# THB.net
KiCad netlist of a schematic drawn in Altium Designer
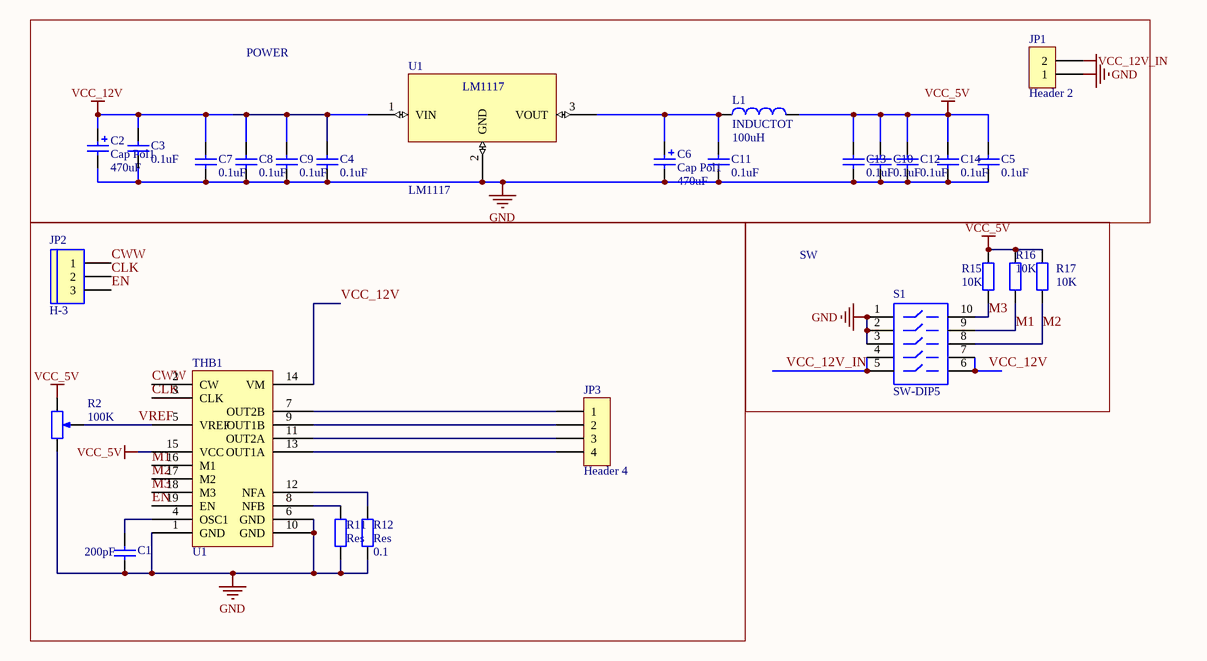
[diagram p0: THB.SchDoc]

(export (version "E")
  (design (tool "Eeschema 10.0.6"))
  (components
    (comp (ref "C1")
      (value "200pF")
      (footprint "CC1005-0402")
      (description "Capacitor")
      (fields
        (field (name "MANUFACTURER") "Generic Components")
        (field (name "Comment") "CAP")
        (field (name "PUBLISHER") "Altium Hobart Technology Centre")
      )
      (libsource (lib "HGH") (part "CAP"))
    )
    (comp (ref "C2")
      (value "Cap Pol1")
      (footprint "diode stan")
      (description "Polarized Capacitor (Radial)")
      (fields
        (field (name "MANUFACTURER") "Generic Components")
        (field (name "ALTIUM_VALUE") "470uF")
        (field (name "PUBLISHER") "Altium Hobart Technology Centre")
      )
      (libsource (lib "HGH") (part "Cap Pol1"))
    )
    (comp (ref "C3")
      (value "0.1uF")
      (footprint "CC1005-0402")
      (description "Capacitor")
      (fields
        (field (name "MANUFACTURER") "Generic Components")
        (field (name "Comment") "CAP_1")
        (field (name "PUBLISHER") "Altium Hobart Technology Centre")
      )
      (libsource (lib "My SchLib") (part "CAP_1"))
    )
    (comp (ref "C4")
      (value "0.1uF")
      (footprint "CC1005-0402")
      (description "Capacitor")
      (fields
        (field (name "MANUFACTURER") "Generic Components")
        (field (name "Comment") "CAP")
        (field (name "PUBLISHER") "Altium Hobart Technology Centre")
      )
      (libsource (lib "HGH") (part "CAP"))
    )
    (comp (ref "C5")
      (value "0.1uF")
      (footprint "CC1005-0402")
      (description "Capacitor")
      (fields
        (field (name "MANUFACTURER") "Generic Components")
        (field (name "Comment") "CAP")
        (field (name "PUBLISHER") "Altium Hobart Technology Centre")
      )
      (libsource (lib "HGH") (part "CAP"))
    )
    (comp (ref "C6")
      (value "Cap Pol1")
      (footprint "diode stan")
      (description "Polarized Capacitor (Radial)")
      (fields
        (field (name "MANUFACTURER") "Generic Components")
        (field (name "ALTIUM_VALUE") "470uF")
        (field (name "PUBLISHER") "Altium Hobart Technology Centre")
      )
      (libsource (lib "HGH") (part "Cap Pol1"))
    )
    (comp (ref "C7")
      (value "0.1uF")
      (footprint "CC1005-0402")
      (description "Capacitor")
      (fields
        (field (name "MANUFACTURER") "Generic Components")
        (field (name "Comment") "CAP_1")
        (field (name "PUBLISHER") "Altium Hobart Technology Centre")
      )
      (libsource (lib "My SchLib") (part "CAP_1"))
    )
    (comp (ref "C8")
      (value "0.1uF")
      (footprint "CC1005-0402")
      (description "Capacitor")
      (fields
        (field (name "MANUFACTURER") "Generic Components")
        (field (name "Comment") "CAP_1")
        (field (name "PUBLISHER") "Altium Hobart Technology Centre")
      )
      (libsource (lib "My SchLib") (part "CAP_1"))
    )
    (comp (ref "C9")
      (value "0.1uF")
      (footprint "CC1005-0402")
      (description "Capacitor")
      (fields
        (field (name "MANUFACTURER") "Generic Components")
        (field (name "Comment") "CAP_1")
        (field (name "PUBLISHER") "Altium Hobart Technology Centre")
      )
      (libsource (lib "My SchLib") (part "CAP_1"))
    )
    (comp (ref "C10")
      (value "0.1uF")
      (footprint "CC1005-0402")
      (description "Capacitor")
      (fields
        (field (name "MANUFACTURER") "Generic Components")
        (field (name "Comment") "CAP_1")
        (field (name "PUBLISHER") "Altium Hobart Technology Centre")
      )
      (libsource (lib "My SchLib") (part "CAP_1"))
    )
    (comp (ref "C11")
      (value "0.1uF")
      (footprint "CC1005-0402")
      (description "Capacitor")
      (fields
        (field (name "MANUFACTURER") "Generic Components")
        (field (name "Comment") "CAP_1")
        (field (name "PUBLISHER") "Altium Hobart Technology Centre")
      )
      (libsource (lib "My SchLib") (part "CAP_1"))
    )
    (comp (ref "C12")
      (value "0.1uF")
      (footprint "CC1005-0402")
      (description "Capacitor")
      (fields
        (field (name "MANUFACTURER") "Generic Components")
        (field (name "Comment") "CAP_1")
        (field (name "PUBLISHER") "Altium Hobart Technology Centre")
      )
      (libsource (lib "My SchLib") (part "CAP_1"))
    )
    (comp (ref "C13")
      (value "0.1uF")
      (footprint "CC1005-0402")
      (description "Capacitor")
      (fields
        (field (name "MANUFACTURER") "Generic Components")
        (field (name "Comment") "CAP_1")
        (field (name "PUBLISHER") "Altium Hobart Technology Centre")
      )
      (libsource (lib "My SchLib") (part "CAP_1"))
    )
    (comp (ref "C14")
      (value "0.1uF")
      (footprint "CC1005-0402")
      (description "Capacitor")
      (fields
        (field (name "MANUFACTURER") "Generic Components")
        (field (name "Comment") "CAP_1")
        (field (name "PUBLISHER") "Altium Hobart Technology Centre")
      )
      (libsource (lib "My SchLib") (part "CAP_1"))
    )
    (comp (ref "JP1")
      (value "Header 2")
      (footprint "HDR1-2")
      (description "Header, 2-Pin")
      (fields (field (name "MANUFACTURER") "Generic Components"))
      (libsource (lib "HGH") (part "Header 2"))
    )
    (comp (ref "JP2")
      (value "H-3")
      (footprint "H- 3")
      (description "Header, 3-Pin")
      (fields (field (name "MANUFACTURER") "Generic Components"))
      (libsource (lib "HGH") (part "H-3"))
    )
    (comp (ref "JP3")
      (value "Header 4")
      (footprint "HDR1-4")
      (description "Header, 4-Pin")
      (fields (field (name "MANUFACTURER") "Generic Components"))
      (libsource (lib "HGH") (part "Header 4"))
    )
    (comp (ref "L1")
      (value "INDUCTOT")
      (footprint "贴片电感")
      (description "Inductor")
      (fields
        (field (name "MANUFACTURER") "Generic Components")
        (field (name "ALTIUM_VALUE") "100uH")
        (field (name "PUBLISHER") "Altium Hobart Technology Centre")
      )
      (libsource (lib "HGH") (part "INDUCTOT"))
    )
    (comp (ref "R2")
      (value "100K")
      (footprint "res-adj-tiepian")
      (description "Potentiometer")
      (fields (field (name "Comment") "RES-Pot2"))
      (libsource (lib "HGH") (part "RES-Pot2"))
    )
    (comp (ref "R11")
      (value "Res")
      (footprint "AXLAL0.4")
      (description "Resistor")
      (fields
        (field (name "MANUFACTURER") "Generic Components")
        (field (name "PUBLISHER") "Altium Hobart Technology Centre")
      )
      (libsource (lib "HGH") (part "Res"))
    )
    (comp (ref "R12")
      (value "Res")
      (footprint "AXLAL0.4")
      (description "Resistor")
      (fields
        (field (name "MANUFACTURER") "Generic Components")
        (field (name "ALTIUM_VALUE") "0.1")
        (field (name "PUBLISHER") "Altium Hobart Technology Centre")
      )
      (libsource (lib "HGH") (part "Res"))
    )
    (comp (ref "R15")
      (value "10K")
      (footprint "R2012-0805")
      (description "Resistor")
      (fields
        (field (name "MANUFACTURER") "Generic Components")
        (field (name "Comment") "Res")
        (field (name "PUBLISHER") "Altium Hobart Technology Centre")
      )
      (libsource (lib "HGH") (part "Res"))
    )
    (comp (ref "R16")
      (value "10K")
      (footprint "R2012-0805")
      (description "Resistor")
      (fields
        (field (name "MANUFACTURER") "Generic Components")
        (field (name "Comment") "Res")
        (field (name "PUBLISHER") "Altium Hobart Technology Centre")
      )
      (libsource (lib "HGH") (part "Res"))
    )
    (comp (ref "R17")
      (value "10K")
      (footprint "R2012-0805")
      (description "Resistor")
      (fields
        (field (name "MANUFACTURER") "Generic Components")
        (field (name "Comment") "Res")
        (field (name "PUBLISHER") "Altium Hobart Technology Centre")
      )
      (libsource (lib "HGH") (part "Res"))
    )
    (comp (ref "S1")
      (value "SW-DIP5")
      (footprint "SW-5")
      (description "DIP Switch,5-bit")
      (fields (field (name "MANUFACTURER") "Generic Components"))
      (libsource (lib "HGH") (part "SW-DIP5"))
    )
    (comp (ref "THB1") (value "U1") (footprint "THB7218") (libsource (lib "HGH") (part "THB7128")))
    (comp (ref "U1") (value "LM1117") (footprint "DSO-G3/P2.3") (libsource (lib "HGH") (part "LM1117")))
  )
  (nets
    (net (code "1") (name "/CLK") (class "Default")
      (node (ref "JP2") (pin "2") (pinfunction "2_2") (pintype "passive"))
      (node (ref "THB1") (pin "3") (pinfunction "CLK_3") (pintype "passive"))
    )
    (net (code "2") (name "/CWW") (class "Default")
      (node (ref "JP2") (pin "1") (pinfunction "1_1") (pintype "passive"))
      (node (ref "THB1") (pin "2") (pinfunction "CW_2") (pintype "passive"))
    )
    (net (code "3") (name "/EN") (class "Default")
      (node (ref "JP2") (pin "3") (pinfunction "3_3") (pintype "passive"))
      (node (ref "THB1") (pin "19") (pinfunction "EN_19") (pintype "passive"))
    )
    (net (code "4") (name "/M1") (class "Default")
      (node (ref "R16") (pin "1") (pinfunction "1_1") (pintype "passive"))
      (node (ref "S1") (pin "9") (pinfunction "9_9") (pintype "passive"))
      (node (ref "THB1") (pin "16") (pinfunction "M1_16") (pintype "passive"))
    )
    (net (code "5") (name "/M2") (class "Default")
      (node (ref "R17") (pin "1") (pinfunction "1_1") (pintype "passive"))
      (node (ref "S1") (pin "8") (pinfunction "8_8") (pintype "passive"))
      (node (ref "THB1") (pin "17") (pinfunction "M2_17") (pintype "passive"))
    )
    (net (code "6") (name "/M3") (class "Default")
      (node (ref "R15") (pin "1") (pinfunction "1_1") (pintype "passive"))
      (node (ref "S1") (pin "10") (pinfunction "10_10") (pintype "passive"))
      (node (ref "THB1") (pin "18") (pinfunction "M3_18") (pintype "passive"))
    )
    (net (code "7") (name "/VREF") (class "Default")
      (node (ref "R2") (pin "2") (pinfunction "TAP_2") (pintype "passive"))
      (node (ref "THB1") (pin "5") (pinfunction "VREF_5") (pintype "passive"))
    )
    (net (code "8") (name "GND") (class "Default")
      (node (ref "C1") (pin "1") (pinfunction "1_1") (pintype "passive"))
      (node (ref "C10") (pin "1") (pinfunction "1_1") (pintype "passive"))
      (node (ref "C11") (pin "1") (pinfunction "1_1") (pintype "passive"))
      (node (ref "C12") (pin "1") (pinfunction "1_1") (pintype "passive"))
      (node (ref "C13") (pin "1") (pinfunction "1_1") (pintype "passive"))
      (node (ref "C14") (pin "1") (pinfunction "1_1") (pintype "passive"))
      (node (ref "C2") (pin "2") (pinfunction "2_2") (pintype "passive"))
      (node (ref "C3") (pin "1") (pinfunction "1_1") (pintype "passive"))
      (node (ref "C4") (pin "1") (pinfunction "1_1") (pintype "passive"))
      (node (ref "C5") (pin "1") (pinfunction "1_1") (pintype "passive"))
      (node (ref "C6") (pin "2") (pinfunction "2_2") (pintype "passive"))
      (node (ref "C7") (pin "1") (pinfunction "1_1") (pintype "passive"))
      (node (ref "C8") (pin "1") (pinfunction "1_1") (pintype "passive"))
      (node (ref "C9") (pin "1") (pinfunction "1_1") (pintype "passive"))
      (node (ref "JP1") (pin "1") (pinfunction "1_1") (pintype "passive"))
      (node (ref "R11") (pin "1") (pinfunction "1_1") (pintype "passive"))
      (node (ref "R12") (pin "1") (pinfunction "1_1") (pintype "passive"))
      (node (ref "R2") (pin "3") (pinfunction "TOP_3") (pintype "passive"))
      (node (ref "S1") (pin "1") (pinfunction "1_1") (pintype "passive"))
      (node (ref "S1") (pin "2") (pinfunction "2_2") (pintype "passive"))
      (node (ref "S1") (pin "3") (pinfunction "3_3") (pintype "passive"))
      (node (ref "THB1") (pin "1") (pinfunction "GND_1") (pintype "passive"))
      (node (ref "THB1") (pin "10") (pinfunction "GND_10") (pintype "passive"))
      (node (ref "THB1") (pin "6") (pinfunction "GND_6") (pintype "passive"))
      (node (ref "U1") (pin "2") (pinfunction "GND_2") (pintype "bidirectional"))
    )
    (net (code "9") (name "Net-(THB1-NFA)") (class "Default")
      (node (ref "R12") (pin "2") (pinfunction "2_2") (pintype "passive"))
      (node (ref "THB1") (pin "12") (pinfunction "NFA_12") (pintype "passive"))
    )
    (net (code "10") (name "Net-(THB1-NFB)") (class "Default")
      (node (ref "R11") (pin "2") (pinfunction "2_2") (pintype "passive"))
      (node (ref "THB1") (pin "8") (pinfunction "NFB_8") (pintype "passive"))
    )
    (net (code "11") (name "Net-(THB1-OSC1)") (class "Default")
      (node (ref "C1") (pin "2") (pinfunction "2_2") (pintype "passive"))
      (node (ref "THB1") (pin "4") (pinfunction "OSC1_4") (pintype "passive"))
    )
    (net (code "12") (name "Net-(THB1-OUT1A)") (class "Default")
      (node (ref "JP3") (pin "4") (pinfunction "4_4") (pintype "passive"))
      (node (ref "THB1") (pin "13") (pinfunction "OUT1A_13") (pintype "passive"))
    )
    (net (code "13") (name "Net-(THB1-OUT1B)") (class "Default")
      (node (ref "JP3") (pin "2") (pinfunction "2_2") (pintype "passive"))
      (node (ref "THB1") (pin "9") (pinfunction "OUT1B_9") (pintype "passive"))
    )
    (net (code "14") (name "Net-(THB1-OUT2A)") (class "Default")
      (node (ref "JP3") (pin "3") (pinfunction "3_3") (pintype "passive"))
      (node (ref "THB1") (pin "11") (pinfunction "OUT2A_11") (pintype "passive"))
    )
    (net (code "15") (name "Net-(THB1-OUT2B)") (class "Default")
      (node (ref "JP3") (pin "1") (pinfunction "1_1") (pintype "passive"))
      (node (ref "THB1") (pin "7") (pinfunction "OUT2B_7") (pintype "passive"))
    )
    (net (code "16") (name "Net-(U1-VOUT)") (class "Default")
      (node (ref "C11") (pin "2") (pinfunction "2_2") (pintype "passive"))
      (node (ref "C6") (pin "1") (pinfunction "1_1") (pintype "passive"))
      (node (ref "L1") (pin "1") (pinfunction "1_1") (pintype "passive"))
      (node (ref "U1") (pin "3") (pinfunction "VOUT_3") (pintype "bidirectional"))
    )
    (net (code "17") (name "VCC_5V") (class "Default")
      (node (ref "C10") (pin "2") (pinfunction "2_2") (pintype "passive"))
      (node (ref "C12") (pin "2") (pinfunction "2_2") (pintype "passive"))
      (node (ref "C13") (pin "2") (pinfunction "2_2") (pintype "passive"))
      (node (ref "C14") (pin "2") (pinfunction "2_2") (pintype "passive"))
      (node (ref "C5") (pin "2") (pinfunction "2_2") (pintype "passive"))
      (node (ref "L1") (pin "2") (pinfunction "2_2") (pintype "passive"))
      (node (ref "R15") (pin "2") (pinfunction "2_2") (pintype "passive"))
      (node (ref "R16") (pin "2") (pinfunction "2_2") (pintype "passive"))
      (node (ref "R17") (pin "2") (pinfunction "2_2") (pintype "passive"))
      (node (ref "R2") (pin "1") (pinfunction "BOT_1") (pintype "passive"))
      (node (ref "THB1") (pin "15") (pinfunction "VCC_15") (pintype "passive"))
    )
    (net (code "18") (name "VCC_12V") (class "Default")
      (node (ref "C2") (pin "1") (pinfunction "1_1") (pintype "passive"))
      (node (ref "C3") (pin "2") (pinfunction "2_2") (pintype "passive"))
      (node (ref "C4") (pin "2") (pinfunction "2_2") (pintype "passive"))
      (node (ref "C7") (pin "2") (pinfunction "2_2") (pintype "passive"))
      (node (ref "C8") (pin "2") (pinfunction "2_2") (pintype "passive"))
      (node (ref "C9") (pin "2") (pinfunction "2_2") (pintype "passive"))
      (node (ref "S1") (pin "6") (pinfunction "6_6") (pintype "passive"))
      (node (ref "S1") (pin "7") (pinfunction "7_7") (pintype "passive"))
      (node (ref "THB1") (pin "14") (pinfunction "VM_14") (pintype "passive"))
      (node (ref "U1") (pin "1") (pinfunction "VIN_1") (pintype "bidirectional"))
    )
    (net (code "19") (name "VCC_12V_IN") (class "Default")
      (node (ref "JP1") (pin "2") (pinfunction "2_2") (pintype "passive"))
      (node (ref "S1") (pin "4") (pinfunction "4_4") (pintype "passive"))
      (node (ref "S1") (pin "5") (pinfunction "5_5") (pintype "passive"))
    )
  )
)
